# led_serial_strip_small.net
KiCad netlist of a schematic drawn in EAGLE
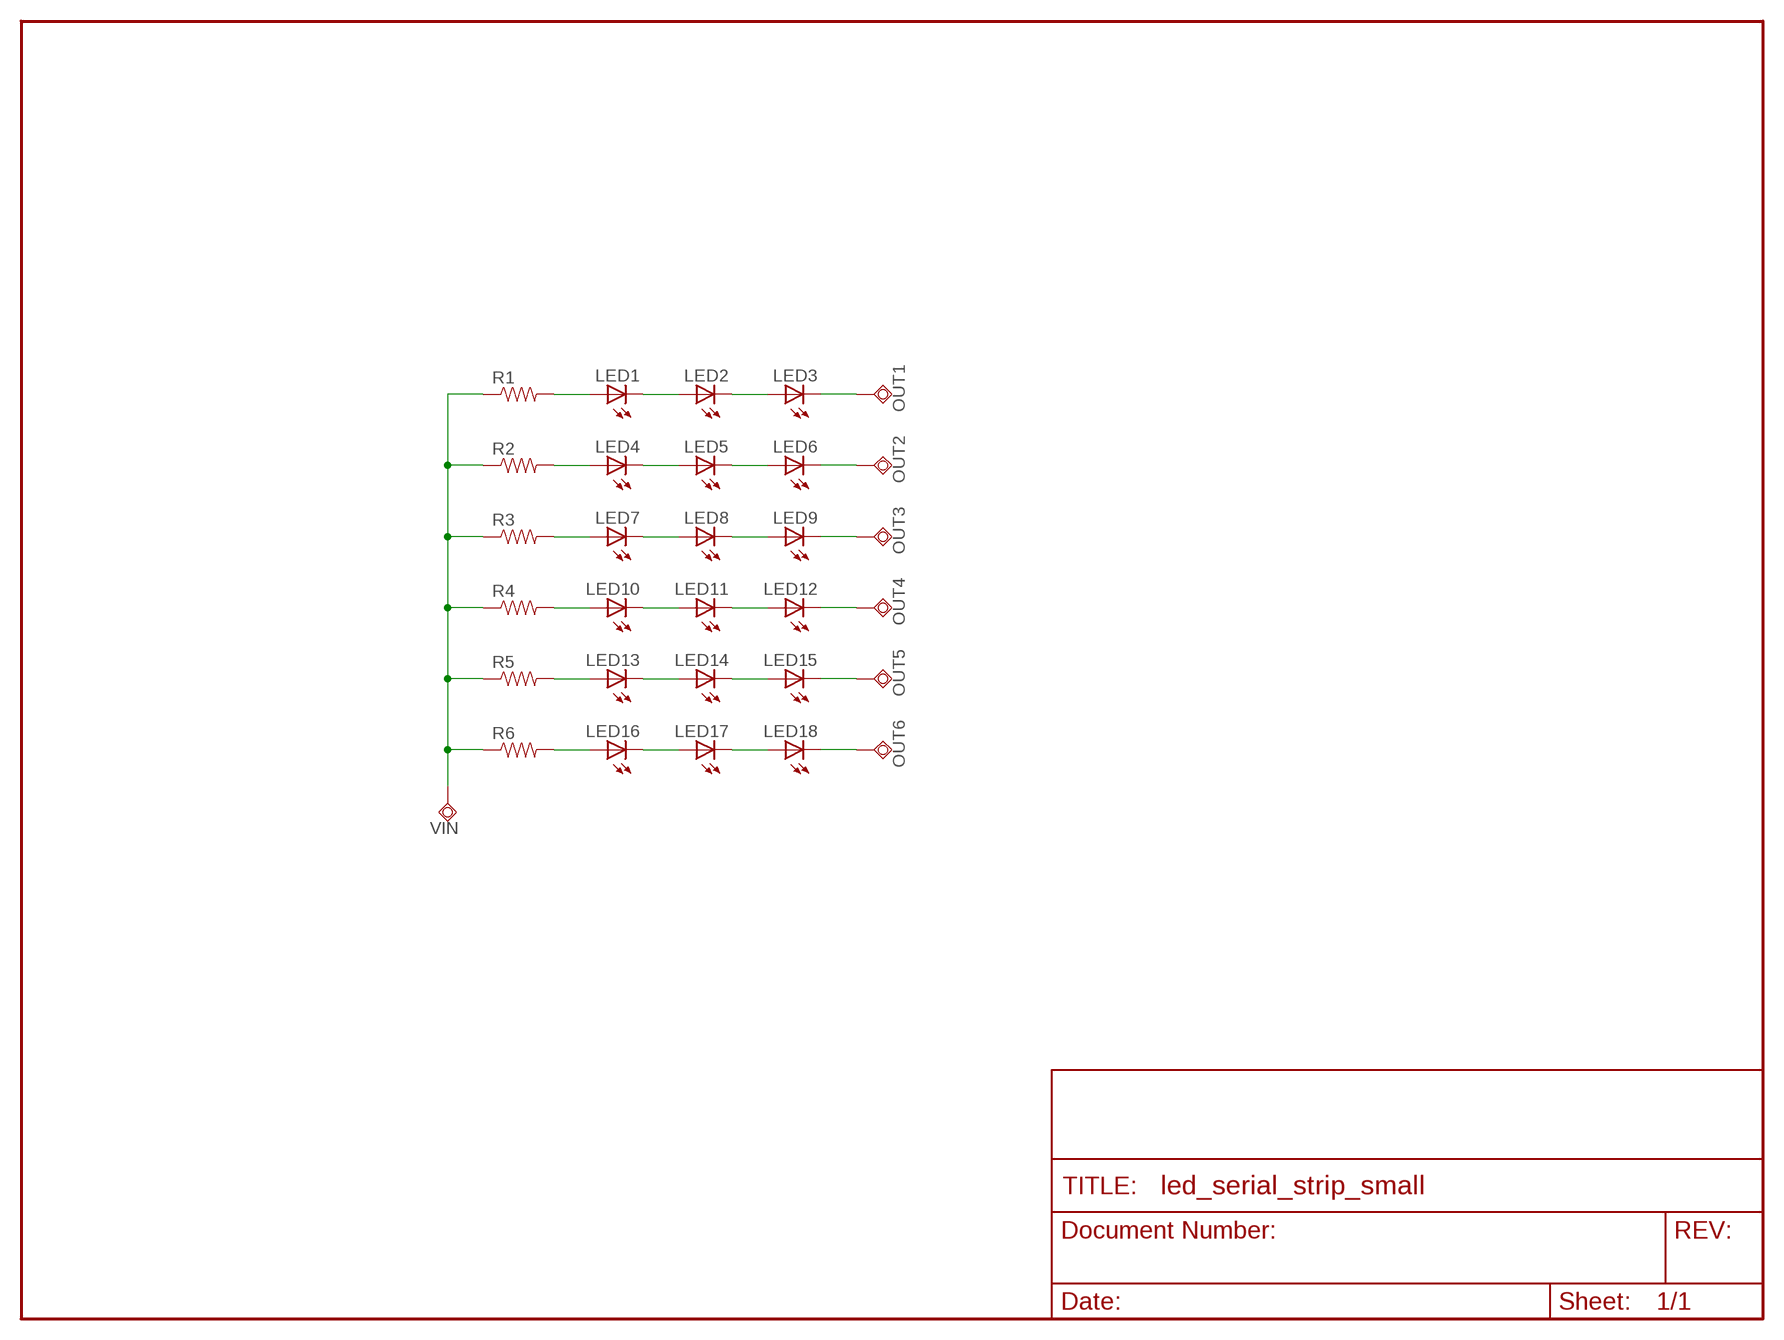
[diagram p0: schematic, sheet 1]

(export (version "E")
  (design (tool "Eeschema 10.0.6"))
  (components
    (comp (ref "LED1")
      (value "LED0805")
      (footprint "eagle-import:LED_0805")
      (libsource (lib "eagle-import") (part "LED0805"))
    )
    (comp (ref "LED2")
      (value "LED0805")
      (footprint "eagle-import:LED_0805")
      (libsource (lib "eagle-import") (part "LED0805"))
    )
    (comp (ref "LED3")
      (value "LED0805")
      (footprint "eagle-import:LED_0805")
      (libsource (lib "eagle-import") (part "LED0805"))
    )
    (comp (ref "LED4")
      (value "LED0805")
      (footprint "eagle-import:LED_0805")
      (libsource (lib "eagle-import") (part "LED0805"))
    )
    (comp (ref "LED5")
      (value "LED0805")
      (footprint "eagle-import:LED_0805")
      (libsource (lib "eagle-import") (part "LED0805"))
    )
    (comp (ref "LED6")
      (value "LED0805")
      (footprint "eagle-import:LED_0805")
      (libsource (lib "eagle-import") (part "LED0805"))
    )
    (comp (ref "LED7")
      (value "LED0805")
      (footprint "eagle-import:LED_0805")
      (libsource (lib "eagle-import") (part "LED0805"))
    )
    (comp (ref "LED8")
      (value "LED0805")
      (footprint "eagle-import:LED_0805")
      (libsource (lib "eagle-import") (part "LED0805"))
    )
    (comp (ref "LED9")
      (value "LED0805")
      (footprint "eagle-import:LED_0805")
      (libsource (lib "eagle-import") (part "LED0805"))
    )
    (comp (ref "LED10")
      (value "LED0805")
      (footprint "eagle-import:LED_0805")
      (libsource (lib "eagle-import") (part "LED0805"))
    )
    (comp (ref "LED11")
      (value "LED0805")
      (footprint "eagle-import:LED_0805")
      (libsource (lib "eagle-import") (part "LED0805"))
    )
    (comp (ref "LED12")
      (value "LED0805")
      (footprint "eagle-import:LED_0805")
      (libsource (lib "eagle-import") (part "LED0805"))
    )
    (comp (ref "LED13")
      (value "LED0805")
      (footprint "eagle-import:LED_0805")
      (libsource (lib "eagle-import") (part "LED0805"))
    )
    (comp (ref "LED14")
      (value "LED0805")
      (footprint "eagle-import:LED_0805")
      (libsource (lib "eagle-import") (part "LED0805"))
    )
    (comp (ref "LED15")
      (value "LED0805")
      (footprint "eagle-import:LED_0805")
      (libsource (lib "eagle-import") (part "LED0805"))
    )
    (comp (ref "LED16")
      (value "LED0805")
      (footprint "eagle-import:LED_0805")
      (libsource (lib "eagle-import") (part "LED0805"))
    )
    (comp (ref "LED17")
      (value "LED0805")
      (footprint "eagle-import:LED_0805")
      (libsource (lib "eagle-import") (part "LED0805"))
    )
    (comp (ref "LED18")
      (value "LED0805")
      (footprint "eagle-import:LED_0805")
      (libsource (lib "eagle-import") (part "LED0805"))
    )
    (comp (ref "OUT1")
      (value "TPSQTP15SQ")
      (footprint "eagle-import:TP15SQ")
      (libsource (lib "eagle-import") (part "TPSQTP15SQ"))
    )
    (comp (ref "OUT2")
      (value "TPSQTP15SQ")
      (footprint "eagle-import:TP15SQ")
      (libsource (lib "eagle-import") (part "TPSQTP15SQ"))
    )
    (comp (ref "OUT3")
      (value "TPSQTP15SQ")
      (footprint "eagle-import:TP15SQ")
      (libsource (lib "eagle-import") (part "TPSQTP15SQ"))
    )
    (comp (ref "OUT4")
      (value "TPSQTP15SQ")
      (footprint "eagle-import:TP15SQ")
      (libsource (lib "eagle-import") (part "TPSQTP15SQ"))
    )
    (comp (ref "OUT5")
      (value "TPSQTP15SQ")
      (footprint "eagle-import:TP15SQ")
      (libsource (lib "eagle-import") (part "TPSQTP15SQ"))
    )
    (comp (ref "OUT6")
      (value "TPSQTP15SQ")
      (footprint "eagle-import:TP15SQ")
      (libsource (lib "eagle-import") (part "TPSQTP15SQ"))
    )
    (comp (ref "R1")
      (value "RESISTOR0805-RES")
      (footprint "eagle-import:0805")
      (libsource (lib "eagle-import") (part "RESISTOR0805-RES"))
    )
    (comp (ref "R2")
      (value "RESISTOR0805-RES")
      (footprint "eagle-import:0805")
      (libsource (lib "eagle-import") (part "RESISTOR0805-RES"))
    )
    (comp (ref "R3")
      (value "RESISTOR0805-RES")
      (footprint "eagle-import:0805")
      (libsource (lib "eagle-import") (part "RESISTOR0805-RES"))
    )
    (comp (ref "R4")
      (value "RESISTOR0805-RES")
      (footprint "eagle-import:0805")
      (libsource (lib "eagle-import") (part "RESISTOR0805-RES"))
    )
    (comp (ref "R5")
      (value "RESISTOR0805-RES")
      (footprint "eagle-import:0805")
      (libsource (lib "eagle-import") (part "RESISTOR0805-RES"))
    )
    (comp (ref "R6")
      (value "RESISTOR0805-RES")
      (footprint "eagle-import:0805")
      (libsource (lib "eagle-import") (part "RESISTOR0805-RES"))
    )
    (comp (ref "VIN")
      (value "TPSQTP15SQ")
      (footprint "eagle-import:TP15SQ")
      (libsource (lib "eagle-import") (part "TPSQTP15SQ"))
    )
  )
  (nets
    (net (code "1") (name "Net-(LED1-PadA)") (class "Default")
      (node (ref "LED1") (pin "A") (pinfunction "A_A") (pintype "passive"))
      (node (ref "R1") (pin "2") (pinfunction "2_2") (pintype "passive"))
    )
    (net (code "2") (name "Net-(LED1-PadC)") (class "Default")
      (node (ref "LED1") (pin "C") (pinfunction "C_C") (pintype "passive"))
      (node (ref "LED2") (pin "A") (pinfunction "A_A") (pintype "passive"))
    )
    (net (code "3") (name "Net-(LED2-PadC)") (class "Default")
      (node (ref "LED2") (pin "C") (pinfunction "C_C") (pintype "passive"))
      (node (ref "LED3") (pin "A") (pinfunction "A_A") (pintype "passive"))
    )
    (net (code "4") (name "Net-(LED3-PadC)") (class "Default")
      (node (ref "LED3") (pin "C") (pinfunction "C_C") (pintype "passive"))
      (node (ref "OUT1") (pin "TP") (pinfunction "TP_TP") (pintype "input"))
    )
    (net (code "5") (name "Net-(LED4-PadA)") (class "Default")
      (node (ref "LED4") (pin "A") (pinfunction "A_A") (pintype "passive"))
      (node (ref "R2") (pin "2") (pinfunction "2_2") (pintype "passive"))
    )
    (net (code "6") (name "Net-(LED4-PadC)") (class "Default")
      (node (ref "LED4") (pin "C") (pinfunction "C_C") (pintype "passive"))
      (node (ref "LED5") (pin "A") (pinfunction "A_A") (pintype "passive"))
    )
    (net (code "7") (name "Net-(LED5-PadC)") (class "Default")
      (node (ref "LED5") (pin "C") (pinfunction "C_C") (pintype "passive"))
      (node (ref "LED6") (pin "A") (pinfunction "A_A") (pintype "passive"))
    )
    (net (code "8") (name "Net-(LED6-PadC)") (class "Default")
      (node (ref "LED6") (pin "C") (pinfunction "C_C") (pintype "passive"))
      (node (ref "OUT2") (pin "TP") (pinfunction "TP_TP") (pintype "input"))
    )
    (net (code "9") (name "Net-(LED7-PadA)") (class "Default")
      (node (ref "LED7") (pin "A") (pinfunction "A_A") (pintype "passive"))
      (node (ref "R3") (pin "2") (pinfunction "2_2") (pintype "passive"))
    )
    (net (code "10") (name "Net-(LED7-PadC)") (class "Default")
      (node (ref "LED7") (pin "C") (pinfunction "C_C") (pintype "passive"))
      (node (ref "LED8") (pin "A") (pinfunction "A_A") (pintype "passive"))
    )
    (net (code "11") (name "Net-(LED8-PadC)") (class "Default")
      (node (ref "LED8") (pin "C") (pinfunction "C_C") (pintype "passive"))
      (node (ref "LED9") (pin "A") (pinfunction "A_A") (pintype "passive"))
    )
    (net (code "12") (name "Net-(LED9-PadC)") (class "Default")
      (node (ref "LED9") (pin "C") (pinfunction "C_C") (pintype "passive"))
      (node (ref "OUT3") (pin "TP") (pinfunction "TP_TP") (pintype "input"))
    )
    (net (code "13") (name "Net-(LED10-PadA)") (class "Default")
      (node (ref "LED10") (pin "A") (pinfunction "A_A") (pintype "passive"))
      (node (ref "R4") (pin "2") (pinfunction "2_2") (pintype "passive"))
    )
    (net (code "14") (name "Net-(LED10-PadC)") (class "Default")
      (node (ref "LED10") (pin "C") (pinfunction "C_C") (pintype "passive"))
      (node (ref "LED11") (pin "A") (pinfunction "A_A") (pintype "passive"))
    )
    (net (code "15") (name "Net-(LED11-PadC)") (class "Default")
      (node (ref "LED11") (pin "C") (pinfunction "C_C") (pintype "passive"))
      (node (ref "LED12") (pin "A") (pinfunction "A_A") (pintype "passive"))
    )
    (net (code "16") (name "Net-(LED12-PadC)") (class "Default")
      (node (ref "LED12") (pin "C") (pinfunction "C_C") (pintype "passive"))
      (node (ref "OUT4") (pin "TP") (pinfunction "TP_TP") (pintype "input"))
    )
    (net (code "17") (name "Net-(LED13-PadA)") (class "Default")
      (node (ref "LED13") (pin "A") (pinfunction "A_A") (pintype "passive"))
      (node (ref "R5") (pin "2") (pinfunction "2_2") (pintype "passive"))
    )
    (net (code "18") (name "Net-(LED13-PadC)") (class "Default")
      (node (ref "LED13") (pin "C") (pinfunction "C_C") (pintype "passive"))
      (node (ref "LED14") (pin "A") (pinfunction "A_A") (pintype "passive"))
    )
    (net (code "19") (name "Net-(LED14-PadC)") (class "Default")
      (node (ref "LED14") (pin "C") (pinfunction "C_C") (pintype "passive"))
      (node (ref "LED15") (pin "A") (pinfunction "A_A") (pintype "passive"))
    )
    (net (code "20") (name "Net-(LED15-PadC)") (class "Default")
      (node (ref "LED15") (pin "C") (pinfunction "C_C") (pintype "passive"))
      (node (ref "OUT5") (pin "TP") (pinfunction "TP_TP") (pintype "input"))
    )
    (net (code "21") (name "Net-(LED16-PadA)") (class "Default")
      (node (ref "LED16") (pin "A") (pinfunction "A_A") (pintype "passive"))
      (node (ref "R6") (pin "2") (pinfunction "2_2") (pintype "passive"))
    )
    (net (code "22") (name "Net-(LED16-PadC)") (class "Default")
      (node (ref "LED16") (pin "C") (pinfunction "C_C") (pintype "passive"))
      (node (ref "LED17") (pin "A") (pinfunction "A_A") (pintype "passive"))
    )
    (net (code "23") (name "Net-(LED17-PadC)") (class "Default")
      (node (ref "LED17") (pin "C") (pinfunction "C_C") (pintype "passive"))
      (node (ref "LED18") (pin "A") (pinfunction "A_A") (pintype "passive"))
    )
    (net (code "24") (name "Net-(LED18-PadC)") (class "Default")
      (node (ref "LED18") (pin "C") (pinfunction "C_C") (pintype "passive"))
      (node (ref "OUT6") (pin "TP") (pinfunction "TP_TP") (pintype "input"))
    )
    (net (code "25") (name "Net-(R1-Pad1)") (class "Default")
      (node (ref "R1") (pin "1") (pinfunction "1_1") (pintype "passive"))
      (node (ref "R2") (pin "1") (pinfunction "1_1") (pintype "passive"))
      (node (ref "R3") (pin "1") (pinfunction "1_1") (pintype "passive"))
      (node (ref "R4") (pin "1") (pinfunction "1_1") (pintype "passive"))
      (node (ref "R5") (pin "1") (pinfunction "1_1") (pintype "passive"))
      (node (ref "R6") (pin "1") (pinfunction "1_1") (pintype "passive"))
      (node (ref "VIN") (pin "TP") (pinfunction "TP_TP") (pintype "input"))
    )
  )
)
